# DAC.net
KiCad netlist of a schematic drawn in Altium Designer
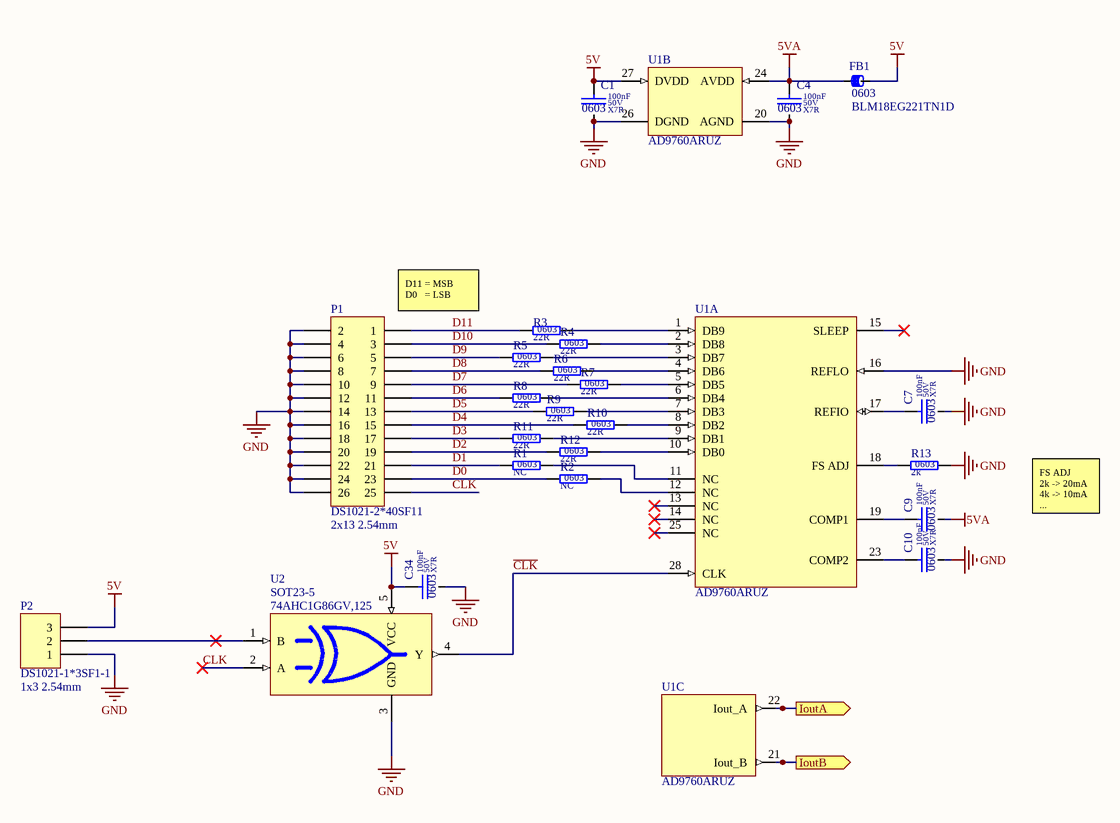
[diagram p0: DAC.SchDoc]

(export (version "E")
  (design (tool "Eeschema 10.0.6"))
  (components
    (comp (ref "C1")
      (value "100nF")
      (footprint "C_0603_1608")
      (description "Capacitor")
      (fields
        (field (name "DIELECTRIC") "X7R")
        (field (name "VOLTAGE") "50V")
        (field (name "SCH_FOOTPRINT") "0603")
        (field (name "PART NUMBER") "C_100nF_50V_X7R_0603_5")
        (field (name "MANUFACTURER") "Samsung")
      )
      (libsource (lib "Library") (part "C"))
    )
    (comp (ref "C4")
      (value "100nF")
      (footprint "C_0603_1608")
      (description "Capacitor")
      (fields
        (field (name "DIELECTRIC") "X7R")
        (field (name "VOLTAGE") "50V")
        (field (name "SCH_FOOTPRINT") "0603")
        (field (name "PART NUMBER") "C_100nF_50V_X7R_0603_5")
        (field (name "MANUFACTURER") "Samsung")
      )
      (libsource (lib "Library") (part "C"))
    )
    (comp (ref "C7")
      (value "100nF")
      (footprint "C_0603_1608")
      (description "Capacitor")
      (fields
        (field (name "DIELECTRIC") "X7R")
        (field (name "VOLTAGE") "50V")
        (field (name "SCH_FOOTPRINT") "0603")
        (field (name "PART NUMBER") "C_100nF_50V_X7R_0603_5")
        (field (name "MANUFACTURER") "Samsung")
      )
      (libsource (lib "Library") (part "C"))
    )
    (comp (ref "C9")
      (value "100nF")
      (footprint "C_0603_1608")
      (description "Capacitor")
      (fields
        (field (name "DIELECTRIC") "X7R")
        (field (name "VOLTAGE") "50V")
        (field (name "SCH_FOOTPRINT") "0603")
        (field (name "PART NUMBER") "C_100nF_50V_X7R_0603_5")
        (field (name "MANUFACTURER") "Samsung")
      )
      (libsource (lib "Library") (part "C"))
    )
    (comp (ref "C10")
      (value "100nF")
      (footprint "C_0603_1608")
      (description "Capacitor")
      (fields
        (field (name "DIELECTRIC") "X7R")
        (field (name "VOLTAGE") "50V")
        (field (name "SCH_FOOTPRINT") "0603")
        (field (name "PART NUMBER") "C_100nF_50V_X7R_0603_5")
        (field (name "MANUFACTURER") "Samsung")
      )
      (libsource (lib "Library") (part "C"))
    )
    (comp (ref "C34")
      (value "100nF")
      (footprint "C_0603_1608")
      (description "Capacitor")
      (fields
        (field (name "DIELECTRIC") "X7R")
        (field (name "VOLTAGE") "50V")
        (field (name "SCH_FOOTPRINT") "0603")
        (field (name "PART NUMBER") "C_100nF_50V_X7R_0603_5")
        (field (name "MANUFACTURER") "Samsung")
      )
      (libsource (lib "Library") (part "C"))
    )
    (comp (ref "FB1")
      (value "BLM18EG221TN1D")
      (footprint "FB_0603_1608")
      (description "Ferrite Bead")
      (fields
        (field (name "PART NUMBER") "FB_BLM18EG221TN1D")
        (field (name "SCH_FOOTPRINT") "0603")
        (field (name "MANUFACTURER") "Murata")
      )
      (libsource (lib "Library") (part "FB"))
    )
    (comp (ref "P1")
      (value "DS1021-2*40SF11")
      (footprint "P_HEADER_2x13_2.54")
      (description "Header, 26-Pin, Dual row")
      (fields
        (field (name "PART NUMBER") "P_HEADER_2x13_2.54")
        (field (name "SCH_FOOTPRINT") "2x13 2.54mm")
        (field (name "MANUFACTURER") "Connfly")
      )
      (libsource (lib "Library") (part "P_HEADER_2x13"))
    )
    (comp (ref "P2")
      (value "DS1021-1*3SF1-1")
      (footprint "P_HEADER_1x3_2.54")
      (description "Header, 3-Pin")
      (fields
        (field (name "PART NUMBER") "P_HEADER_1x3_2.54")
        (field (name "SCH_FOOTPRINT") "1x3 2.54mm")
        (field (name "MANUFACTURER") "Connfly")
      )
      (libsource (lib "Library") (part "P_HEADER_1x3"))
    )
    (comp (ref "R1")
      (value "NC")
      (footprint "R_NC_0603_1608")
      (fields
        (field (name "SCH_FOOTPRINT") "0603")
        (field (name "PART NUMBER") "R_GENERIC_0603")
        (field (name "Comment") "Resistor")
      )
      (libsource (lib "Library") (part "R"))
    )
    (comp (ref "R2")
      (value "NC")
      (footprint "R_NC_0603_1608")
      (fields
        (field (name "SCH_FOOTPRINT") "0603")
        (field (name "PART NUMBER") "R_GENERIC_0603")
        (field (name "Comment") "Resistor")
      )
      (libsource (lib "Library") (part "R"))
    )
    (comp (ref "R3")
      (value "22R")
      (footprint "R_0603_1608")
      (fields
        (field (name "SCH_FOOTPRINT") "0603")
        (field (name "PART NUMBER") "R_22R_0603_5")
        (field (name "VOLTAGE") "50V")
        (field (name "POWER") "125mW")
      )
      (libsource (lib "Library") (part "R"))
    )
    (comp (ref "R4")
      (value "22R")
      (footprint "R_0603_1608")
      (fields
        (field (name "SCH_FOOTPRINT") "0603")
        (field (name "PART NUMBER") "R_22R_0603_5")
        (field (name "VOLTAGE") "50V")
        (field (name "POWER") "125mW")
      )
      (libsource (lib "Library") (part "R"))
    )
    (comp (ref "R5")
      (value "22R")
      (footprint "R_0603_1608")
      (fields
        (field (name "SCH_FOOTPRINT") "0603")
        (field (name "PART NUMBER") "R_22R_0603_5")
        (field (name "VOLTAGE") "50V")
        (field (name "POWER") "125mW")
      )
      (libsource (lib "Library") (part "R"))
    )
    (comp (ref "R6")
      (value "22R")
      (footprint "R_0603_1608")
      (fields
        (field (name "SCH_FOOTPRINT") "0603")
        (field (name "PART NUMBER") "R_22R_0603_5")
        (field (name "VOLTAGE") "50V")
        (field (name "POWER") "125mW")
      )
      (libsource (lib "Library") (part "R"))
    )
    (comp (ref "R7")
      (value "22R")
      (footprint "R_0603_1608")
      (fields
        (field (name "SCH_FOOTPRINT") "0603")
        (field (name "PART NUMBER") "R_22R_0603_5")
        (field (name "VOLTAGE") "50V")
        (field (name "POWER") "125mW")
      )
      (libsource (lib "Library") (part "R"))
    )
    (comp (ref "R8")
      (value "22R")
      (footprint "R_0603_1608")
      (fields
        (field (name "SCH_FOOTPRINT") "0603")
        (field (name "PART NUMBER") "R_22R_0603_5")
        (field (name "VOLTAGE") "50V")
        (field (name "POWER") "125mW")
      )
      (libsource (lib "Library") (part "R"))
    )
    (comp (ref "R9")
      (value "22R")
      (footprint "R_0603_1608")
      (fields
        (field (name "SCH_FOOTPRINT") "0603")
        (field (name "PART NUMBER") "R_22R_0603_5")
        (field (name "VOLTAGE") "50V")
        (field (name "POWER") "125mW")
      )
      (libsource (lib "Library") (part "R"))
    )
    (comp (ref "R10")
      (value "22R")
      (footprint "R_0603_1608")
      (fields
        (field (name "SCH_FOOTPRINT") "0603")
        (field (name "PART NUMBER") "R_22R_0603_5")
        (field (name "VOLTAGE") "50V")
        (field (name "POWER") "125mW")
      )
      (libsource (lib "Library") (part "R"))
    )
    (comp (ref "R11")
      (value "22R")
      (footprint "R_0603_1608")
      (fields
        (field (name "SCH_FOOTPRINT") "0603")
        (field (name "PART NUMBER") "R_22R_0603_5")
        (field (name "VOLTAGE") "50V")
        (field (name "POWER") "125mW")
      )
      (libsource (lib "Library") (part "R"))
    )
    (comp (ref "R12")
      (value "22R")
      (footprint "R_0603_1608")
      (fields
        (field (name "SCH_FOOTPRINT") "0603")
        (field (name "PART NUMBER") "R_22R_0603_5")
        (field (name "VOLTAGE") "50V")
        (field (name "POWER") "125mW")
      )
      (libsource (lib "Library") (part "R"))
    )
    (comp (ref "R13")
      (value "2k")
      (footprint "R_0603_1608")
      (fields
        (field (name "SCH_FOOTPRINT") "0603")
        (field (name "PART NUMBER") "R_2k_0603_1")
        (field (name "VOLTAGE") "50V")
        (field (name "POWER") "100mW")
      )
      (libsource (lib "Library") (part "R"))
    )
    (comp (ref "U1")
      (value "AD9760ARUZ")
      (footprint "TSSOP28_EP_4X10X12")
      (description "10-Bit 125Msps DACs")
      (fields (field (name "PART NUMBER") "U_AD9760ARUZ") (field (name "MANUFACTURER") "Analog Devices"))
      (libsource (lib "Library") (part "U_AD9760"))
    )
    (comp (ref "U2")
      (value "74AHC1G86GV,125")
      (footprint "SOT23-5_SC74A_SOT753_M")
      (fields
        (field (name "SCH_FOOTPRINT") "SOT23-5")
        (field (name "PART NUMBER") "U_74AHC1G86GV.125")
        (field (name "MANUFACTURER") "Nexperia")
        (field (name "Comment") "2-input EXCLUSIVE-OR gate")
      )
      (libsource (lib "Library") (part "U_74AHC1G86"))
    )
  )
  (nets
    (net (code "1") (name "/CLK") (class "Default")
      (node (ref "P1") (pin "25") (pinfunction "25_25") (pintype "passive"))
      (node (ref "U2") (pin "2") (pinfunction "A_2") (pintype "input"))
    )
    (net (code "2") (name "/D0") (class "Default")
      (node (ref "P1") (pin "23") (pinfunction "23_23") (pintype "passive"))
      (node (ref "R2") (pin "1") (pinfunction "1_1") (pintype "passive"))
    )
    (net (code "3") (name "/D1") (class "Default")
      (node (ref "P1") (pin "21") (pinfunction "21_21") (pintype "passive"))
      (node (ref "R1") (pin "1") (pinfunction "1_1") (pintype "passive"))
    )
    (net (code "4") (name "/D2") (class "Default")
      (node (ref "P1") (pin "19") (pinfunction "19_19") (pintype "passive"))
      (node (ref "R12") (pin "1") (pinfunction "1_1") (pintype "passive"))
    )
    (net (code "5") (name "/D3") (class "Default")
      (node (ref "P1") (pin "17") (pinfunction "17_17") (pintype "passive"))
      (node (ref "R11") (pin "1") (pinfunction "1_1") (pintype "passive"))
    )
    (net (code "6") (name "/D4") (class "Default")
      (node (ref "P1") (pin "15") (pinfunction "15_15") (pintype "passive"))
      (node (ref "R10") (pin "1") (pinfunction "1_1") (pintype "passive"))
    )
    (net (code "7") (name "/D5") (class "Default")
      (node (ref "P1") (pin "13") (pinfunction "13_13") (pintype "passive"))
      (node (ref "R9") (pin "1") (pinfunction "1_1") (pintype "passive"))
    )
    (net (code "8") (name "/D6") (class "Default")
      (node (ref "P1") (pin "11") (pinfunction "11_11") (pintype "passive"))
      (node (ref "R8") (pin "1") (pinfunction "1_1") (pintype "passive"))
    )
    (net (code "9") (name "/D7") (class "Default")
      (node (ref "P1") (pin "9") (pinfunction "9_9") (pintype "passive"))
      (node (ref "R7") (pin "1") (pinfunction "1_1") (pintype "passive"))
    )
    (net (code "10") (name "/D8") (class "Default")
      (node (ref "P1") (pin "7") (pinfunction "7_7") (pintype "passive"))
      (node (ref "R6") (pin "1") (pinfunction "1_1") (pintype "passive"))
    )
    (net (code "11") (name "/D9") (class "Default")
      (node (ref "P1") (pin "5") (pinfunction "5_5") (pintype "passive"))
      (node (ref "R5") (pin "1") (pinfunction "1_1") (pintype "passive"))
    )
    (net (code "12") (name "/D10") (class "Default")
      (node (ref "P1") (pin "3") (pinfunction "3_3") (pintype "passive"))
      (node (ref "R4") (pin "1") (pinfunction "1_1") (pintype "passive"))
    )
    (net (code "13") (name "/D11") (class "Default")
      (node (ref "P1") (pin "1") (pinfunction "1_1") (pintype "passive"))
      (node (ref "R3") (pin "1") (pinfunction "1_1") (pintype "passive"))
    )
    (net (code "14") (name "/IoutA") (class "Default")
      (node (ref "U1") (pin "22") (pinfunction "Iout_A_22") (pintype "output"))
    )
    (net (code "15") (name "/IoutB") (class "Default")
      (node (ref "U1") (pin "21") (pinfunction "Iout_B_21") (pintype "output"))
    )
    (net (code "16") (name "/~{CLK}") (class "Default")
      (node (ref "U1") (pin "28") (pinfunction "CLK_28") (pintype "input"))
      (node (ref "U2") (pin "4") (pinfunction "Y_4") (pintype "output"))
    )
    (net (code "17") (name "5V") (class "Default")
      (node (ref "C1") (pin "1") (pinfunction "1_1") (pintype "passive"))
      (node (ref "C34") (pin "1") (pinfunction "1_1") (pintype "passive"))
      (node (ref "FB1") (pin "2") (pintype "passive"))
      (node (ref "P2") (pin "3") (pinfunction "3_3") (pintype "passive"))
      (node (ref "U1") (pin "27") (pinfunction "DVDD_27") (pintype "input"))
      (node (ref "U2") (pin "5") (pinfunction "VCC_5") (pintype "input"))
    )
    (net (code "18") (name "5VA") (class "Default")
      (node (ref "C4") (pin "1") (pinfunction "1_1") (pintype "passive"))
      (node (ref "C9") (pin "2") (pinfunction "2_2") (pintype "passive"))
      (node (ref "FB1") (pin "1") (pintype "passive"))
      (node (ref "U1") (pin "24") (pinfunction "AVDD_24") (pintype "input"))
    )
    (net (code "19") (name "GND") (class "Default")
      (node (ref "C1") (pin "2") (pinfunction "2_2") (pintype "passive"))
      (node (ref "C10") (pin "2") (pinfunction "2_2") (pintype "passive"))
      (node (ref "C34") (pin "2") (pinfunction "2_2") (pintype "passive"))
      (node (ref "C4") (pin "2") (pinfunction "2_2") (pintype "passive"))
      (node (ref "C7") (pin "2") (pinfunction "2_2") (pintype "passive"))
      (node (ref "P1") (pin "10") (pinfunction "10_10") (pintype "passive"))
      (node (ref "P1") (pin "12") (pinfunction "12_12") (pintype "passive"))
      (node (ref "P1") (pin "14") (pinfunction "14_14") (pintype "passive"))
      (node (ref "P1") (pin "16") (pinfunction "16_16") (pintype "passive"))
      (node (ref "P1") (pin "18") (pinfunction "18_18") (pintype "passive"))
      (node (ref "P1") (pin "2") (pinfunction "2_2") (pintype "passive"))
      (node (ref "P1") (pin "20") (pinfunction "20_20") (pintype "passive"))
      (node (ref "P1") (pin "22") (pinfunction "22_22") (pintype "passive"))
      (node (ref "P1") (pin "24") (pinfunction "24_24") (pintype "passive"))
      (node (ref "P1") (pin "26") (pinfunction "26_26") (pintype "passive"))
      (node (ref "P1") (pin "4") (pinfunction "4_4") (pintype "passive"))
      (node (ref "P1") (pin "6") (pinfunction "6_6") (pintype "passive"))
      (node (ref "P1") (pin "8") (pinfunction "8_8") (pintype "passive"))
      (node (ref "P2") (pin "1") (pinfunction "1_1") (pintype "passive"))
      (node (ref "R13") (pin "2") (pinfunction "2_2") (pintype "passive"))
      (node (ref "U1") (pin "16") (pinfunction "REFLO_16") (pintype "input"))
      (node (ref "U1") (pin "20") (pinfunction "AGND_20") (pintype "power_in"))
      (node (ref "U1") (pin "26") (pinfunction "DGND_26") (pintype "power_in"))
      (node (ref "U2") (pin "3") (pinfunction "GND_3") (pintype "power_in"))
    )
    (net (code "20") (name "Net-(R1-Pad2)") (class "Default")
      (node (ref "R1") (pin "2") (pinfunction "2_2") (pintype "passive"))
      (node (ref "U1") (pin "11") (pinfunction "NC_11") (pintype "passive"))
    )
    (net (code "21") (name "Net-(R2-Pad2)") (class "Default")
      (node (ref "R2") (pin "2") (pinfunction "2_2") (pintype "passive"))
      (node (ref "U1") (pin "12") (pinfunction "NC_12") (pintype "passive"))
    )
    (net (code "22") (name "Net-(U1A-COMP1)") (class "Default")
      (node (ref "C9") (pin "1") (pinfunction "1_1") (pintype "passive"))
      (node (ref "U1") (pin "19") (pinfunction "COMP1_19") (pintype "passive"))
    )
    (net (code "23") (name "Net-(U1A-COMP2)") (class "Default")
      (node (ref "C10") (pin "1") (pinfunction "1_1") (pintype "passive"))
      (node (ref "U1") (pin "23") (pinfunction "COMP2_23") (pintype "passive"))
    )
    (net (code "24") (name "Net-(U1A-DB0)") (class "Default")
      (node (ref "R12") (pin "2") (pinfunction "2_2") (pintype "passive"))
      (node (ref "U1") (pin "10") (pinfunction "DB0_10") (pintype "input"))
    )
    (net (code "25") (name "Net-(U1A-DB1)") (class "Default")
      (node (ref "R11") (pin "2") (pinfunction "2_2") (pintype "passive"))
      (node (ref "U1") (pin "9") (pinfunction "DB1_9") (pintype "input"))
    )
    (net (code "26") (name "Net-(U1A-DB2)") (class "Default")
      (node (ref "R10") (pin "2") (pinfunction "2_2") (pintype "passive"))
      (node (ref "U1") (pin "8") (pinfunction "DB2_8") (pintype "input"))
    )
    (net (code "27") (name "Net-(U1A-DB3)") (class "Default")
      (node (ref "R9") (pin "2") (pinfunction "2_2") (pintype "passive"))
      (node (ref "U1") (pin "7") (pinfunction "DB3_7") (pintype "input"))
    )
    (net (code "28") (name "Net-(U1A-DB4)") (class "Default")
      (node (ref "R8") (pin "2") (pinfunction "2_2") (pintype "passive"))
      (node (ref "U1") (pin "6") (pinfunction "DB4_6") (pintype "input"))
    )
    (net (code "29") (name "Net-(U1A-DB5)") (class "Default")
      (node (ref "R7") (pin "2") (pinfunction "2_2") (pintype "passive"))
      (node (ref "U1") (pin "5") (pinfunction "DB5_5") (pintype "input"))
    )
    (net (code "30") (name "Net-(U1A-DB6)") (class "Default")
      (node (ref "R6") (pin "2") (pinfunction "2_2") (pintype "passive"))
      (node (ref "U1") (pin "4") (pinfunction "DB6_4") (pintype "input"))
    )
    (net (code "31") (name "Net-(U1A-DB7)") (class "Default")
      (node (ref "R5") (pin "2") (pinfunction "2_2") (pintype "passive"))
      (node (ref "U1") (pin "3") (pinfunction "DB7_3") (pintype "input"))
    )
    (net (code "32") (name "Net-(U1A-DB8)") (class "Default")
      (node (ref "R4") (pin "2") (pinfunction "2_2") (pintype "passive"))
      (node (ref "U1") (pin "2") (pinfunction "DB8_2") (pintype "input"))
    )
    (net (code "33") (name "Net-(U1A-DB9)") (class "Default")
      (node (ref "R3") (pin "2") (pinfunction "2_2") (pintype "passive"))
      (node (ref "U1") (pin "1") (pinfunction "DB9_1") (pintype "input"))
    )
    (net (code "34") (name "Net-(U1A-FS_ADJ)") (class "Default")
      (node (ref "R13") (pin "1") (pinfunction "1_1") (pintype "passive"))
      (node (ref "U1") (pin "18") (pinfunction "FS_ADJ_18") (pintype "passive"))
    )
    (net (code "35") (name "Net-(U1A-REFIO)") (class "Default")
      (node (ref "C7") (pin "1") (pinfunction "1_1") (pintype "passive"))
      (node (ref "U1") (pin "17") (pinfunction "REFIO_17") (pintype "bidirectional"))
    )
    (net (code "36") (name "Net-(U2-B)") (class "Default")
      (node (ref "P2") (pin "2") (pinfunction "2_2") (pintype "passive"))
      (node (ref "U2") (pin "1") (pinfunction "B_1") (pintype "input"))
    )
    (net (code "37") (name "unconnected-(U1A-NC-Pad13)") (class "Default")
      (node (ref "U1") (pin "13") (pinfunction "NC_13") (pintype "passive+no_connect"))
    )
    (net (code "38") (name "unconnected-(U1A-NC-Pad14)") (class "Default")
      (node (ref "U1") (pin "14") (pinfunction "NC_14") (pintype "passive+no_connect"))
    )
    (net (code "39") (name "unconnected-(U1A-NC-Pad25)") (class "Default")
      (node (ref "U1") (pin "25") (pinfunction "NC_25") (pintype "passive+no_connect"))
    )
    (net (code "40") (name "unconnected-(U1A-SLEEP-Pad15)") (class "Default")
      (node (ref "U1") (pin "15") (pinfunction "SLEEP_15") (pintype "passive+no_connect"))
    )
  )
)
